# accelerometer.net
KiCad netlist of a schematic drawn in EAGLE
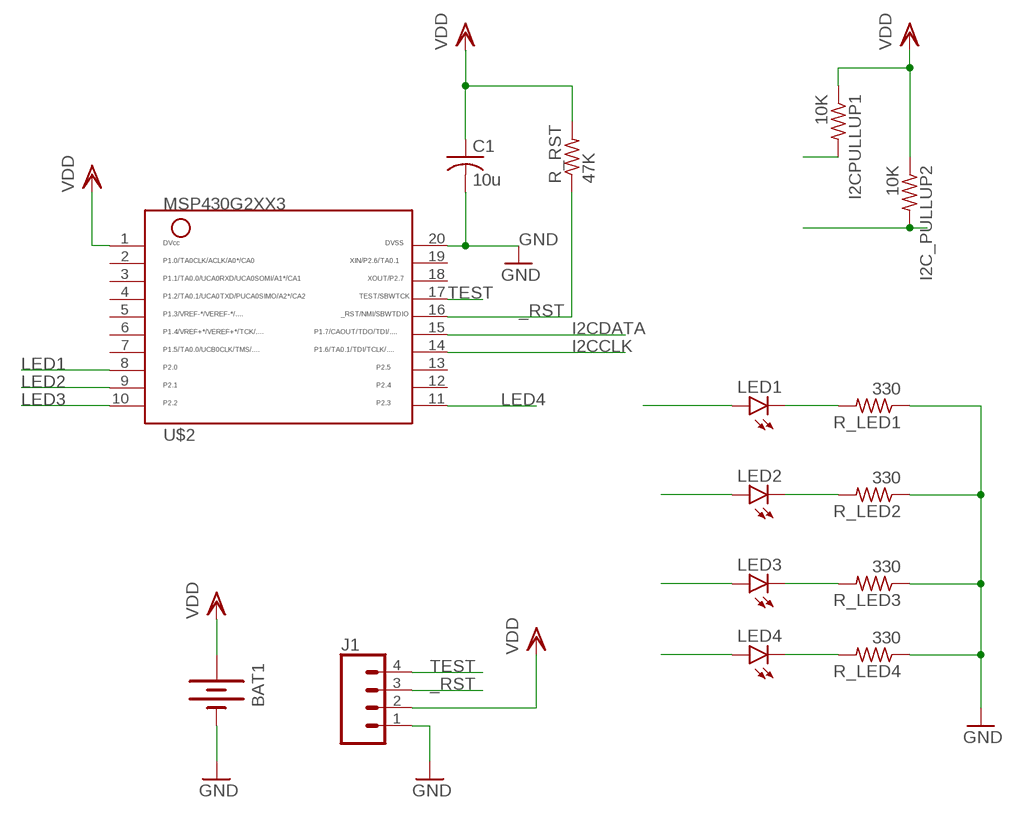
[diagram p0: schematic, sheet 1]

(export (version "E")
  (design (tool "Eeschema 10.0.6"))
  (components
    (comp (ref "BAT1")
      (value "BATTERYBU2032SM")
      (footprint "eagle-import:BU2032SM")
      (libsource (lib "eagle-import") (part "BATTERYBU2032SM"))
    )
    (comp (ref "C1")
      (value "10u")
      (footprint "eagle-import:C1206")
      (libsource (lib "eagle-import") (part "C-USC1206"))
    )
    (comp (ref "I2CPULLUP1")
      (value "10K")
      (footprint "eagle-import:R1206")
      (libsource (lib "eagle-import") (part "R-US_R1206"))
    )
    (comp (ref "I2C_PULLUP2")
      (value "10K")
      (footprint "eagle-import:R1206")
      (libsource (lib "eagle-import") (part "R-US_R1206"))
    )
    (comp (ref "J1")
      (value "CONN_04LOCK")
      (footprint "eagle-import:1X04_LOCK")
      (libsource (lib "eagle-import") (part "CONN_04LOCK"))
    )
    (comp (ref "LED1")
      (value "LEDCHIPLED_1206")
      (footprint "eagle-import:CHIPLED_1206")
      (libsource (lib "eagle-import") (part "LEDCHIPLED_1206"))
    )
    (comp (ref "LED2")
      (value "LEDCHIPLED_1206")
      (footprint "eagle-import:CHIPLED_1206")
      (libsource (lib "eagle-import") (part "LEDCHIPLED_1206"))
    )
    (comp (ref "LED3")
      (value "LEDCHIPLED_1206")
      (footprint "eagle-import:CHIPLED_1206")
      (libsource (lib "eagle-import") (part "LEDCHIPLED_1206"))
    )
    (comp (ref "LED4")
      (value "LEDCHIPLED_1206")
      (footprint "eagle-import:CHIPLED_1206")
      (libsource (lib "eagle-import") (part "LEDCHIPLED_1206"))
    )
    (comp (ref "R_LED1")
      (value "330")
      (footprint "eagle-import:R1206")
      (libsource (lib "eagle-import") (part "R-US_R1206"))
    )
    (comp (ref "R_LED2")
      (value "330")
      (footprint "eagle-import:R1206")
      (libsource (lib "eagle-import") (part "R-US_R1206"))
    )
    (comp (ref "R_LED3")
      (value "330")
      (footprint "eagle-import:R1206")
      (libsource (lib "eagle-import") (part "R-US_R1206"))
    )
    (comp (ref "R_LED4")
      (value "330")
      (footprint "eagle-import:R1206")
      (libsource (lib "eagle-import") (part "R-US_R1206"))
    )
    (comp (ref "R_RST")
      (value "47K")
      (footprint "eagle-import:R1206")
      (libsource (lib "eagle-import") (part "R-US_R1206"))
    )
    (comp (ref "U$2")
      (value "MSP430G2XX3TSSOP")
      (footprint "eagle-import:PW20")
      (libsource (lib "eagle-import") (part "MSP430G2XX3TSSOP"))
    )
  )
  (nets
    (net (code "1") (name "/I2CCLK") (class "Default")
      (node (ref "U$2") (pin "14") (pinfunction "14_14") (pintype "bidirectional"))
    )
    (net (code "2") (name "/I2CDATA") (class "Default")
      (node (ref "U$2") (pin "15") (pinfunction "15_15") (pintype "bidirectional"))
    )
    (net (code "3") (name "/LED1") (class "Default")
      (node (ref "U$2") (pin "8") (pinfunction "8_8") (pintype "bidirectional"))
    )
    (net (code "4") (name "/LED2") (class "Default")
      (node (ref "U$2") (pin "9") (pinfunction "9_9") (pintype "bidirectional"))
    )
    (net (code "5") (name "/LED3") (class "Default")
      (node (ref "U$2") (pin "10") (pinfunction "10_10") (pintype "bidirectional"))
    )
    (net (code "6") (name "/LED4") (class "Default")
      (node (ref "U$2") (pin "11") (pinfunction "11_11") (pintype "bidirectional"))
    )
    (net (code "7") (name "/TEST") (class "Default")
      (node (ref "J1") (pin "4") (pinfunction "4_4") (pintype "passive"))
      (node (ref "U$2") (pin "17") (pinfunction "17_17") (pintype "bidirectional"))
    )
    (net (code "8") (name "/_RST") (class "Default")
      (node (ref "J1") (pin "3") (pinfunction "3_3") (pintype "passive"))
      (node (ref "R_RST") (pin "1") (pinfunction "1_1") (pintype "passive"))
      (node (ref "U$2") (pin "16") (pinfunction "16_16") (pintype "bidirectional"))
    )
    (net (code "9") (name "GND") (class "Default")
      (node (ref "BAT1") (pin "P$2") (pinfunction "-_P$2") (pintype "power_in"))
      (node (ref "C1") (pin "2") (pinfunction "2_2") (pintype "passive"))
      (node (ref "J1") (pin "1") (pinfunction "1_1") (pintype "passive"))
      (node (ref "R_LED1") (pin "1") (pinfunction "1_1") (pintype "passive"))
      (node (ref "R_LED2") (pin "1") (pinfunction "1_1") (pintype "passive"))
      (node (ref "R_LED3") (pin "1") (pinfunction "1_1") (pintype "passive"))
      (node (ref "R_LED4") (pin "1") (pinfunction "1_1") (pintype "passive"))
      (node (ref "U$2") (pin "20") (pinfunction "20_20") (pintype "bidirectional"))
    )
    (net (code "10") (name "Net-(LED1-PadC)") (class "Default")
      (node (ref "LED1") (pin "C") (pinfunction "C_C") (pintype "passive"))
      (node (ref "R_LED1") (pin "2") (pinfunction "2_2") (pintype "passive"))
    )
    (net (code "11") (name "Net-(LED2-PadC)") (class "Default")
      (node (ref "LED2") (pin "C") (pinfunction "C_C") (pintype "passive"))
      (node (ref "R_LED2") (pin "2") (pinfunction "2_2") (pintype "passive"))
    )
    (net (code "12") (name "Net-(LED3-PadC)") (class "Default")
      (node (ref "LED3") (pin "C") (pinfunction "C_C") (pintype "passive"))
      (node (ref "R_LED3") (pin "2") (pinfunction "2_2") (pintype "passive"))
    )
    (net (code "13") (name "Net-(LED4-PadC)") (class "Default")
      (node (ref "LED4") (pin "C") (pinfunction "C_C") (pintype "passive"))
      (node (ref "R_LED4") (pin "2") (pinfunction "2_2") (pintype "passive"))
    )
    (net (code "14") (name "VDD") (class "Default")
      (node (ref "BAT1") (pin "P$1") (pinfunction "+_P$1") (pintype "power_in"))
      (node (ref "C1") (pin "1") (pinfunction "1_1") (pintype "passive"))
      (node (ref "I2CPULLUP1") (pin "1") (pinfunction "1_1") (pintype "passive"))
      (node (ref "I2C_PULLUP2") (pin "1") (pinfunction "1_1") (pintype "passive"))
      (node (ref "J1") (pin "2") (pinfunction "2_2") (pintype "passive"))
      (node (ref "R_RST") (pin "2") (pinfunction "2_2") (pintype "passive"))
      (node (ref "U$2") (pin "1") (pinfunction "1_1") (pintype "bidirectional"))
    )
    (net (code "15") (name "unconnected-(I2CPULLUP1-Pad2)") (class "Default")
      (node (ref "I2CPULLUP1") (pin "2") (pinfunction "2_2") (pintype "passive"))
    )
    (net (code "16") (name "unconnected-(I2C_PULLUP2-Pad2)") (class "Default")
      (node (ref "I2C_PULLUP2") (pin "2") (pinfunction "2_2") (pintype "passive"))
    )
    (net (code "17") (name "unconnected-(LED1-PadA)") (class "Default")
      (node (ref "LED1") (pin "A") (pinfunction "A_A") (pintype "passive"))
    )
    (net (code "18") (name "unconnected-(LED2-PadA)") (class "Default")
      (node (ref "LED2") (pin "A") (pinfunction "A_A") (pintype "passive"))
    )
    (net (code "19") (name "unconnected-(LED3-PadA)") (class "Default")
      (node (ref "LED3") (pin "A") (pinfunction "A_A") (pintype "passive"))
    )
    (net (code "20") (name "unconnected-(LED4-PadA)") (class "Default")
      (node (ref "LED4") (pin "A") (pinfunction "A_A") (pintype "passive"))
    )
    (net (code "21") (name "unconnected-(U$2-Pad2)") (class "Default")
      (node (ref "U$2") (pin "2") (pinfunction "2_2") (pintype "bidirectional"))
    )
    (net (code "22") (name "unconnected-(U$2-Pad3)") (class "Default")
      (node (ref "U$2") (pin "3") (pinfunction "3_3") (pintype "bidirectional"))
    )
    (net (code "23") (name "unconnected-(U$2-Pad4)") (class "Default")
      (node (ref "U$2") (pin "4") (pinfunction "4_4") (pintype "bidirectional"))
    )
    (net (code "24") (name "unconnected-(U$2-Pad5)") (class "Default")
      (node (ref "U$2") (pin "5") (pinfunction "5_5") (pintype "bidirectional"))
    )
    (net (code "25") (name "unconnected-(U$2-Pad6)") (class "Default")
      (node (ref "U$2") (pin "6") (pinfunction "6_6") (pintype "bidirectional"))
    )
    (net (code "26") (name "unconnected-(U$2-Pad7)") (class "Default")
      (node (ref "U$2") (pin "7") (pinfunction "7_7") (pintype "bidirectional"))
    )
    (net (code "27") (name "unconnected-(U$2-Pad12)") (class "Default")
      (node (ref "U$2") (pin "12") (pinfunction "12_12") (pintype "bidirectional"))
    )
    (net (code "28") (name "unconnected-(U$2-Pad13)") (class "Default")
      (node (ref "U$2") (pin "13") (pinfunction "13_13") (pintype "bidirectional"))
    )
    (net (code "29") (name "unconnected-(U$2-Pad18)") (class "Default")
      (node (ref "U$2") (pin "18") (pinfunction "18_18") (pintype "bidirectional"))
    )
    (net (code "30") (name "unconnected-(U$2-Pad19)") (class "Default")
      (node (ref "U$2") (pin "19") (pinfunction "19_19") (pintype "bidirectional"))
    )
  )
)
